# DC-DC_Converters.net
KiCad netlist of a schematic drawn in Altium Designer
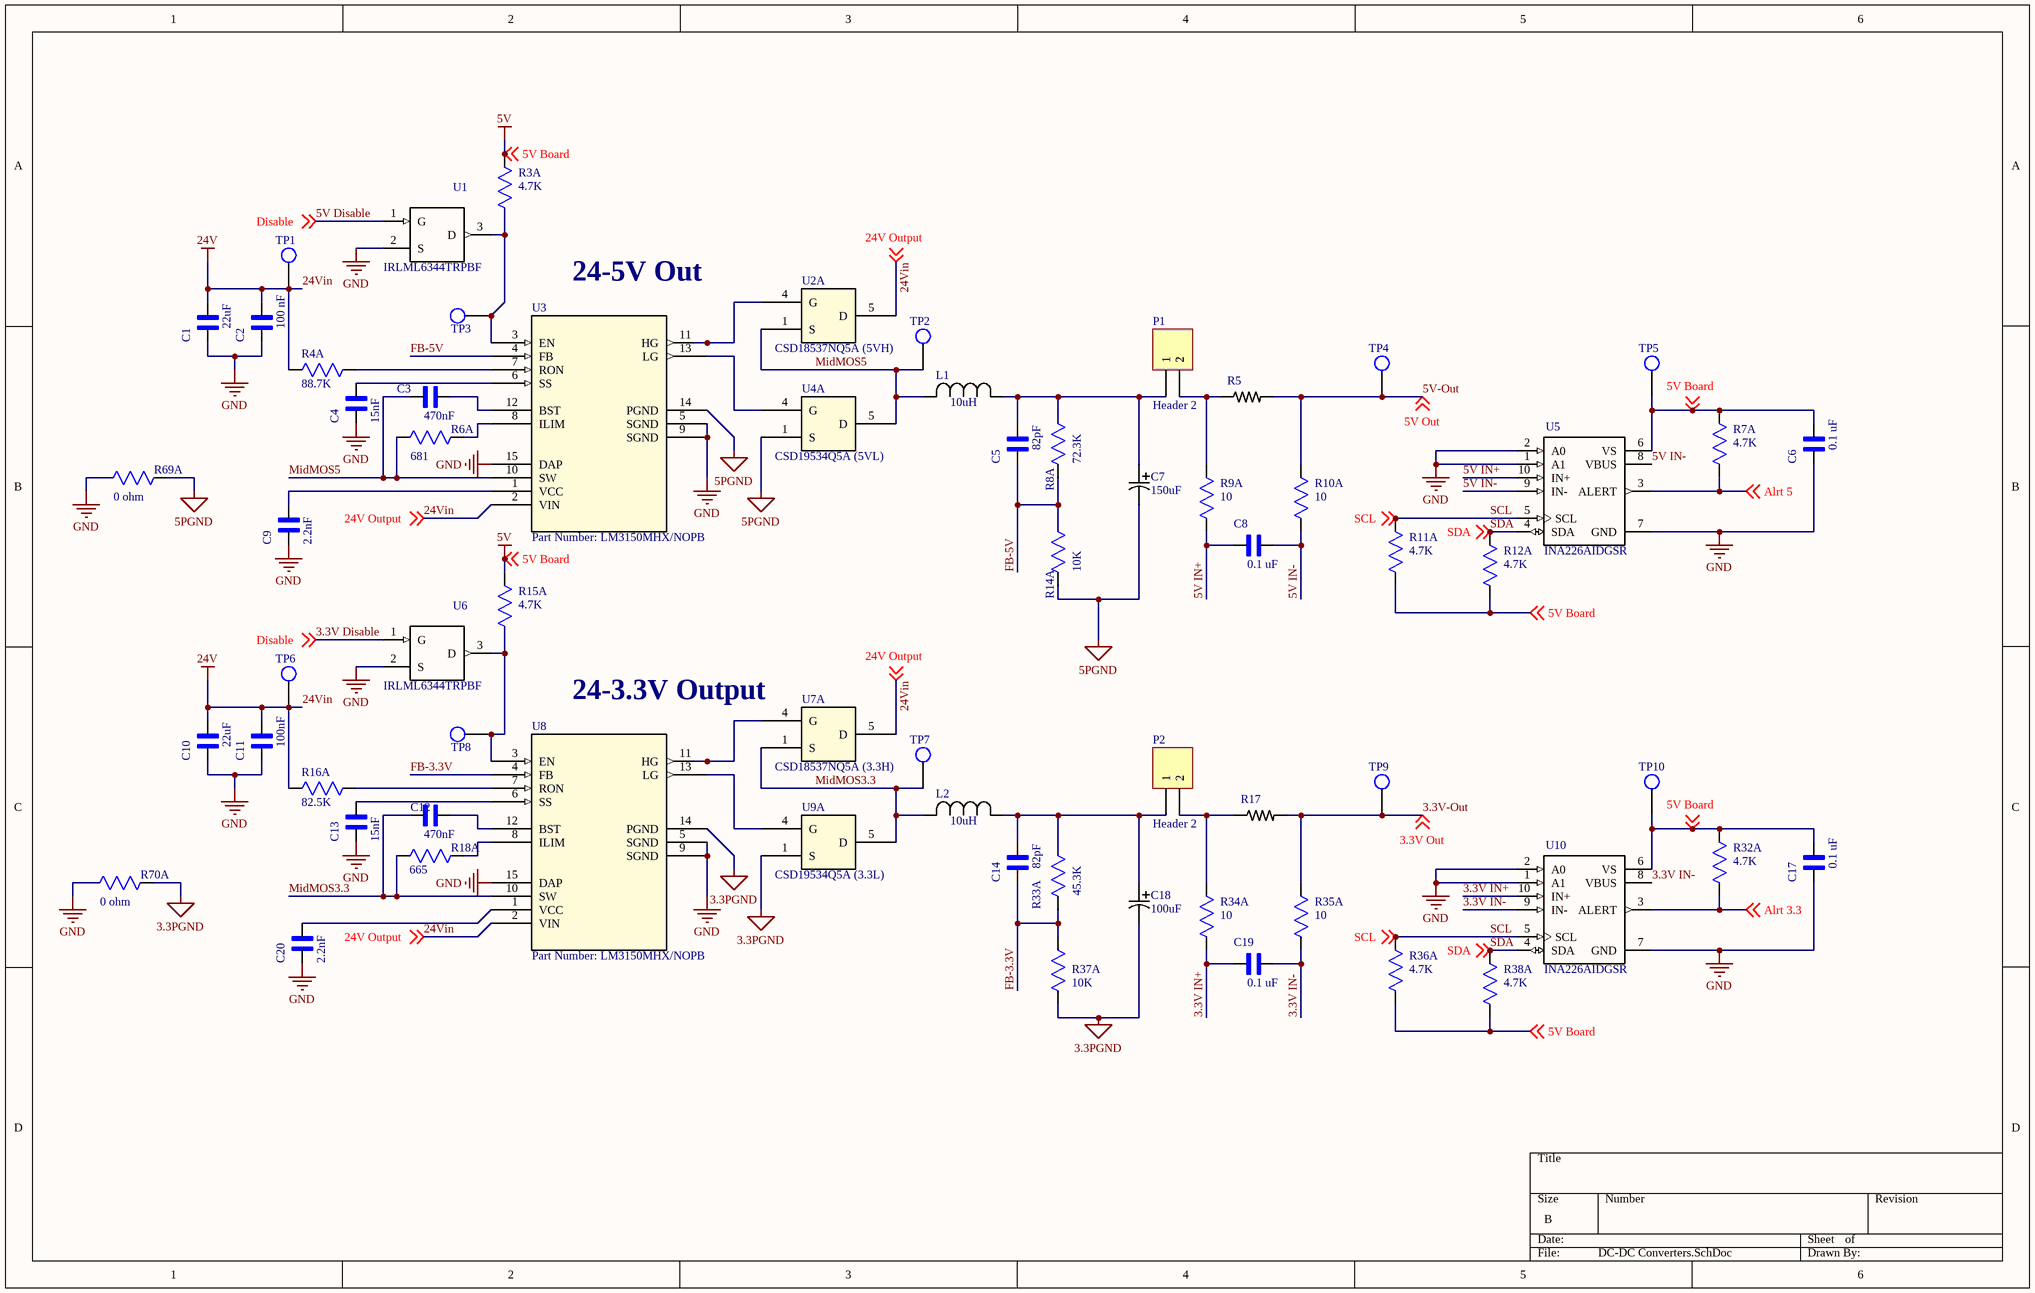
[diagram p0: DC-DC Converters.SchDoc]

(export (version "E")
  (design (tool "Eeschema 10.0.6"))
  (components
    (comp (ref "C1")
      (value "22uF")
      (footprint "*CAPC2012X135N")
      (description "Cap Ceramic 2.2uF 16V X5R 10% SMD 0805 125Â°C Embossed T/R")
      (fields (field (name "MP") "EMK212BJ225KG-T") (field (name "DIGI-KEY_PART_NUMBER") "587-1293-1-ND"))
      (libsource (lib "EMK212BJ225KG-T") (part "EMK212BJ225KG-T"))
    )
    (comp (ref "C2")
      (value "100 nF")
      (footprint "*CAPC2012X135N")
      (description "Cap Ceramic 2.2uF 16V X5R 10% SMD 0805 125Â°C Embossed T/R")
      (fields (field (name "MP") "EMK212BJ225KG-T") (field (name "DIGI-KEY_PART_NUMBER") "587-1293-1-ND"))
      (libsource (lib "EMK212BJ225KG-T") (part "EMK212BJ225KG-T"))
    )
    (comp (ref "C3")
      (value "470nF")
      (footprint "*CAPC2012X135N")
      (description "Cap Ceramic 2.2uF 16V X5R 10% SMD 0805 125Â°C Embossed T/R")
      (fields (field (name "MP") "EMK212BJ225KG-T") (field (name "DIGI-KEY_PART_NUMBER") "587-1293-1-ND"))
      (libsource (lib "EMK212BJ225KG-T") (part "EMK212BJ225KG-T"))
    )
    (comp (ref "C4")
      (value "15nF")
      (footprint "*CAPC2012X135N")
      (description "Cap Ceramic 2.2uF 16V X5R 10% SMD 0805 125Â°C Embossed T/R")
      (fields (field (name "MP") "EMK212BJ225KG-T") (field (name "DIGI-KEY_PART_NUMBER") "587-1293-1-ND"))
      (libsource (lib "EMK212BJ225KG-T") (part "EMK212BJ225KG-T"))
    )
    (comp (ref "C5")
      (value "82pF")
      (footprint "*CAPC2012X135N")
      (description "Cap Ceramic 2.2uF 16V X5R 10% SMD 0805 125Â°C Embossed T/R")
      (fields (field (name "MP") "EMK212BJ225KG-T") (field (name "DIGI-KEY_PART_NUMBER") "587-1293-1-ND"))
      (libsource (lib "EMK212BJ225KG-T") (part "EMK212BJ225KG-T"))
    )
    (comp (ref "C6")
      (value "0.1 uF")
      (footprint "*CAPC2012X135N")
      (description "Cap Ceramic 2.2uF 16V X5R 10% SMD 0805 125Â°C Embossed T/R")
      (fields (field (name "MP") "EMK212BJ225KG-T") (field (name "DIGI-KEY_PART_NUMBER") "587-1293-1-ND"))
      (libsource (lib "EMK212BJ225KG-T") (part "EMK212BJ225KG-T"))
    )
    (comp (ref "C7")
      (value "150uF")
      (footprint "PCAP_TPE_B2")
      (description "No Description Available")
      (fields
        (field (name "MANUFACTURER_PART_NUMBER") "6TPE150MAPB")
        (field (name "COPYRIGHT") "Copyright (C) 2018 Accelerated Designs. All rights reserved")
      )
      (libsource (lib "Pol. Cap 6TPE150MAPB (pkg 1411 (3528 Metric))") (part "6TPE150MAPB"))
    )
    (comp (ref "C8")
      (value "0.1 uF")
      (footprint "*CAPC2012X135N")
      (description "Cap Ceramic 2.2uF 16V X5R 10% SMD 0805 125Â°C Embossed T/R")
      (fields (field (name "MP") "EMK212BJ225KG-T") (field (name "DIGI-KEY_PART_NUMBER") "587-1293-1-ND"))
      (libsource (lib "EMK212BJ225KG-T") (part "EMK212BJ225KG-T"))
    )
    (comp (ref "C9")
      (value "2.2nF")
      (footprint "*CAPC2012X135N")
      (description "Cap Ceramic 2.2uF 16V X5R 10% SMD 0805 125Â°C Embossed T/R")
      (fields (field (name "MP") "EMK212BJ225KG-T") (field (name "DIGI-KEY_PART_NUMBER") "587-1293-1-ND"))
      (libsource (lib "EMK212BJ225KG-T") (part "EMK212BJ225KG-T"))
    )
    (comp (ref "C10")
      (value "22uF")
      (footprint "*CAPC2012X135N")
      (description "Cap Ceramic 2.2uF 16V X5R 10% SMD 0805 125Â°C Embossed T/R")
      (fields (field (name "MP") "EMK212BJ225KG-T") (field (name "DIGI-KEY_PART_NUMBER") "587-1293-1-ND"))
      (libsource (lib "EMK212BJ225KG-T") (part "EMK212BJ225KG-T"))
    )
    (comp (ref "C11")
      (value "100nF")
      (footprint "*CAPC2012X135N")
      (description "Cap Ceramic 2.2uF 16V X5R 10% SMD 0805 125Â°C Embossed T/R")
      (fields (field (name "MP") "EMK212BJ225KG-T") (field (name "DIGI-KEY_PART_NUMBER") "587-1293-1-ND"))
      (libsource (lib "EMK212BJ225KG-T") (part "EMK212BJ225KG-T"))
    )
    (comp (ref "C12")
      (value "470nF")
      (footprint "*CAPC2012X135N")
      (description "Cap Ceramic 2.2uF 16V X5R 10% SMD 0805 125Â°C Embossed T/R")
      (fields (field (name "MP") "EMK212BJ225KG-T") (field (name "DIGI-KEY_PART_NUMBER") "587-1293-1-ND"))
      (libsource (lib "EMK212BJ225KG-T") (part "EMK212BJ225KG-T"))
    )
    (comp (ref "C13")
      (value "15nF")
      (footprint "*CAPC2012X135N")
      (description "Cap Ceramic 2.2uF 16V X5R 10% SMD 0805 125Â°C Embossed T/R")
      (fields (field (name "MP") "EMK212BJ225KG-T") (field (name "DIGI-KEY_PART_NUMBER") "587-1293-1-ND"))
      (libsource (lib "EMK212BJ225KG-T") (part "EMK212BJ225KG-T"))
    )
    (comp (ref "C14")
      (value "82pF")
      (footprint "*CAPC2012X135N")
      (description "Cap Ceramic 2.2uF 16V X5R 10% SMD 0805 125Â°C Embossed T/R")
      (fields (field (name "MP") "EMK212BJ225KG-T") (field (name "DIGI-KEY_PART_NUMBER") "587-1293-1-ND"))
      (libsource (lib "EMK212BJ225KG-T") (part "EMK212BJ225KG-T"))
    )
    (comp (ref "C17")
      (value "0.1 uF")
      (footprint "*CAPC2012X135N")
      (description "Cap Ceramic 2.2uF 16V X5R 10% SMD 0805 125Â°C Embossed T/R")
      (fields (field (name "MP") "EMK212BJ225KG-T") (field (name "DIGI-KEY_PART_NUMBER") "587-1293-1-ND"))
      (libsource (lib "EMK212BJ225KG-T") (part "EMK212BJ225KG-T"))
    )
    (comp (ref "C18")
      (value "100uF")
      (footprint "PCAP_TPE_B2")
      (description "No Description Available")
      (fields
        (field (name "MANUFACTURER_PART_NUMBER") "6TPE150MAPB")
        (field (name "COPYRIGHT") "Copyright (C) 2018 Accelerated Designs. All rights reserved")
      )
      (libsource (lib "Pol. Cap 6TPE150MAPB (pkg 1411 (3528 Metric))") (part "6TPE150MAPB"))
    )
    (comp (ref "C19")
      (value "0.1 uF")
      (footprint "*CAPC2012X135N")
      (description "Cap Ceramic 2.2uF 16V X5R 10% SMD 0805 125Â°C Embossed T/R")
      (fields (field (name "MP") "EMK212BJ225KG-T") (field (name "DIGI-KEY_PART_NUMBER") "587-1293-1-ND"))
      (libsource (lib "EMK212BJ225KG-T") (part "EMK212BJ225KG-T"))
    )
    (comp (ref "C20")
      (value "2.2nF")
      (footprint "*CAPC2012X135N")
      (description "Cap Ceramic 2.2uF 16V X5R 10% SMD 0805 125Â°C Embossed T/R")
      (fields (field (name "MP") "EMK212BJ225KG-T") (field (name "DIGI-KEY_PART_NUMBER") "587-1293-1-ND"))
      (libsource (lib "EMK212BJ225KG-T") (part "EMK212BJ225KG-T"))
    )
    (comp (ref "L1")
      (value "10uH")
      (footprint "IND_BOURNS_SRP12")
      (description "No Description Available")
      (fields
        (field (name "MANUFACTURER_PART_NUMBER") "SRP1250-100M")
        (field (name "COPYRIGHT") "Copyright (C) 2018 Accelerated Designs. All rights reserved")
      )
      (libsource (lib "Inductor SRP1250-100M") (part "SRP1250-100M"))
    )
    (comp (ref "L2")
      (value "10uH")
      (footprint "IND_BOURNS_SRP12")
      (description "No Description Available")
      (fields
        (field (name "MANUFACTURER_PART_NUMBER") "SRP1250-100M")
        (field (name "COPYRIGHT") "Copyright (C) 2018 Accelerated Designs. All rights reserved")
      )
      (libsource (lib "Inductor SRP1250-100M") (part "SRP1250-100M"))
    )
    (comp (ref "P1")
      (value "Header 2")
      (footprint "HDR1X2")
      (description "Header, 2-Pin")
      (fields (field (name "PUBLISHER") "Altium Limited"))
      (libsource (lib "Miscellaneous Connectors") (part "Header 2"))
    )
    (comp (ref "P2")
      (value "Header 2")
      (footprint "HDR1X2")
      (description "Header, 2-Pin")
      (fields (field (name "PUBLISHER") "Altium Limited"))
      (libsource (lib "Miscellaneous Connectors") (part "Header 2"))
    )
    (comp (ref "R3")
      (value "4.7K")
      (footprint "RC0805N")
      (description "No Description Available")
      (fields
        (field (name "MANUFACTURER_PART_NUMBER") "CRCW0805681RFKEA_1")
        (field (name "COPYRIGHT") "Copyright (C) 2018 Accelerated Designs. All rights reserved")
      )
      (libsource (lib "2019-11-21_04-54-07") (part "CRCW0805681RFKEA"))
    )
    (comp (ref "R4")
      (value "88.7K")
      (footprint "RC0805N")
      (description "No Description Available")
      (fields
        (field (name "MANUFACTURER_PART_NUMBER") "CRCW0805681RFKEA_1")
        (field (name "COPYRIGHT") "Copyright (C) 2018 Accelerated Designs. All rights reserved")
      )
      (libsource (lib "2019-11-21_04-54-07") (part "CRCW0805681RFKEA"))
    )
    (comp (ref "R5")
      (value "1-1879378-2")
      (footprint "*RESC6331X70N")
      (description "TLR 2512 2.0W R003 1% 150PPM 2K RL")
      (fields (field (name "MP") "TLR3A20KR003FTDG") (field (name "MF") "TE Connectivity"))
      (libsource (lib "TLR3A20KR003FTDG") (part "TLR3A20KR003FTDG"))
    )
    (comp (ref "R6")
      (value "681")
      (footprint "RC0805N")
      (description "No Description Available")
      (fields
        (field (name "MANUFACTURER_PART_NUMBER") "CRCW0805681RFKEA_1")
        (field (name "COPYRIGHT") "Copyright (C) 2018 Accelerated Designs. All rights reserved")
      )
      (libsource (lib "2019-11-21_04-54-07") (part "CRCW0805681RFKEA"))
    )
    (comp (ref "R7")
      (value "4.7K")
      (footprint "RC0805N")
      (description "No Description Available")
      (fields
        (field (name "MANUFACTURER_PART_NUMBER") "CRCW0805681RFKEA_1")
        (field (name "COPYRIGHT") "Copyright (C) 2018 Accelerated Designs. All rights reserved")
      )
      (libsource (lib "2019-11-21_04-54-07") (part "CRCW0805681RFKEA"))
    )
    (comp (ref "R8")
      (value "72.3K")
      (footprint "RC0805N")
      (description "No Description Available")
      (fields
        (field (name "MANUFACTURER_PART_NUMBER") "CRCW0805681RFKEA_1")
        (field (name "COPYRIGHT") "Copyright (C) 2018 Accelerated Designs. All rights reserved")
      )
      (libsource (lib "2019-11-21_04-54-07") (part "CRCW0805681RFKEA"))
    )
    (comp (ref "R9")
      (value "10")
      (footprint "RC0805N")
      (description "No Description Available")
      (fields
        (field (name "MANUFACTURER_PART_NUMBER") "CRCW0805681RFKEA_1")
        (field (name "COPYRIGHT") "Copyright (C) 2018 Accelerated Designs. All rights reserved")
      )
      (libsource (lib "2019-11-21_04-54-07") (part "CRCW0805681RFKEA"))
    )
    (comp (ref "R10")
      (value "10")
      (footprint "RC0805N")
      (description "No Description Available")
      (fields
        (field (name "MANUFACTURER_PART_NUMBER") "CRCW0805681RFKEA_1")
        (field (name "COPYRIGHT") "Copyright (C) 2018 Accelerated Designs. All rights reserved")
      )
      (libsource (lib "2019-11-21_04-54-07") (part "CRCW0805681RFKEA"))
    )
    (comp (ref "R11")
      (value "4.7K")
      (footprint "RC0805N")
      (description "No Description Available")
      (fields
        (field (name "MANUFACTURER_PART_NUMBER") "CRCW0805681RFKEA_1")
        (field (name "COPYRIGHT") "Copyright (C) 2018 Accelerated Designs. All rights reserved")
      )
      (libsource (lib "2019-11-21_04-54-07") (part "CRCW0805681RFKEA"))
    )
    (comp (ref "R12")
      (value "4.7K")
      (footprint "RC0805N")
      (description "No Description Available")
      (fields
        (field (name "MANUFACTURER_PART_NUMBER") "CRCW0805681RFKEA_1")
        (field (name "COPYRIGHT") "Copyright (C) 2018 Accelerated Designs. All rights reserved")
      )
      (libsource (lib "2019-11-21_04-54-07") (part "CRCW0805681RFKEA"))
    )
    (comp (ref "R14")
      (value "10K")
      (footprint "RC0805N")
      (description "No Description Available")
      (fields
        (field (name "MANUFACTURER_PART_NUMBER") "CRCW0805681RFKEA_1")
        (field (name "COPYRIGHT") "Copyright (C) 2018 Accelerated Designs. All rights reserved")
      )
      (libsource (lib "2019-11-21_04-54-07") (part "CRCW0805681RFKEA"))
    )
    (comp (ref "R15")
      (value "4.7K")
      (footprint "RC0805N")
      (description "No Description Available")
      (fields
        (field (name "MANUFACTURER_PART_NUMBER") "CRCW0805681RFKEA_1")
        (field (name "COPYRIGHT") "Copyright (C) 2018 Accelerated Designs. All rights reserved")
      )
      (libsource (lib "2019-11-21_04-54-07") (part "CRCW0805681RFKEA"))
    )
    (comp (ref "R16")
      (value "82.5K")
      (footprint "RC0805N")
      (description "No Description Available")
      (fields
        (field (name "MANUFACTURER_PART_NUMBER") "CRCW0805681RFKEA_1")
        (field (name "COPYRIGHT") "Copyright (C) 2018 Accelerated Designs. All rights reserved")
      )
      (libsource (lib "2019-11-21_04-54-07") (part "CRCW0805681RFKEA"))
    )
    (comp (ref "R17")
      (value "1-1879378-2")
      (footprint "*RESC6331X70N")
      (description "TLR 2512 2.0W R003 1% 150PPM 2K RL")
      (fields (field (name "MP") "TLR3A20KR003FTDG") (field (name "MF") "TE Connectivity"))
      (libsource (lib "TLR3A20KR003FTDG") (part "TLR3A20KR003FTDG"))
    )
    (comp (ref "R18")
      (value "665")
      (footprint "RC0805N")
      (description "No Description Available")
      (fields
        (field (name "MANUFACTURER_PART_NUMBER") "CRCW0805681RFKEA_1")
        (field (name "COPYRIGHT") "Copyright (C) 2018 Accelerated Designs. All rights reserved")
      )
      (libsource (lib "2019-11-21_04-54-07") (part "CRCW0805681RFKEA"))
    )
    (comp (ref "R32")
      (value "4.7K")
      (footprint "RC0805N")
      (description "No Description Available")
      (fields
        (field (name "MANUFACTURER_PART_NUMBER") "CRCW0805681RFKEA_1")
        (field (name "COPYRIGHT") "Copyright (C) 2018 Accelerated Designs. All rights reserved")
      )
      (libsource (lib "2019-11-21_04-54-07") (part "CRCW0805681RFKEA"))
    )
    (comp (ref "R33")
      (value "45.3K")
      (footprint "RC0805N")
      (description "No Description Available")
      (fields
        (field (name "MANUFACTURER_PART_NUMBER") "CRCW0805681RFKEA_1")
        (field (name "COPYRIGHT") "Copyright (C) 2018 Accelerated Designs. All rights reserved")
      )
      (libsource (lib "2019-11-21_04-54-07") (part "CRCW0805681RFKEA"))
    )
    (comp (ref "R34")
      (value "10")
      (footprint "RC0805N")
      (description "No Description Available")
      (fields
        (field (name "MANUFACTURER_PART_NUMBER") "CRCW0805681RFKEA_1")
        (field (name "COPYRIGHT") "Copyright (C) 2018 Accelerated Designs. All rights reserved")
      )
      (libsource (lib "2019-11-21_04-54-07") (part "CRCW0805681RFKEA"))
    )
    (comp (ref "R35")
      (value "10")
      (footprint "RC0805N")
      (description "No Description Available")
      (fields
        (field (name "MANUFACTURER_PART_NUMBER") "CRCW0805681RFKEA_1")
        (field (name "COPYRIGHT") "Copyright (C) 2018 Accelerated Designs. All rights reserved")
      )
      (libsource (lib "2019-11-21_04-54-07") (part "CRCW0805681RFKEA"))
    )
    (comp (ref "R36")
      (value "4.7K")
      (footprint "RC0805N")
      (description "No Description Available")
      (fields
        (field (name "MANUFACTURER_PART_NUMBER") "CRCW0805681RFKEA_1")
        (field (name "COPYRIGHT") "Copyright (C) 2018 Accelerated Designs. All rights reserved")
      )
      (libsource (lib "2019-11-21_04-54-07") (part "CRCW0805681RFKEA"))
    )
    (comp (ref "R37")
      (value "10K")
      (footprint "RC0805N")
      (description "No Description Available")
      (fields
        (field (name "MANUFACTURER_PART_NUMBER") "CRCW0805681RFKEA_1")
        (field (name "COPYRIGHT") "Copyright (C) 2018 Accelerated Designs. All rights reserved")
      )
      (libsource (lib "2019-11-21_04-54-07") (part "CRCW0805681RFKEA"))
    )
    (comp (ref "R38")
      (value "4.7K")
      (footprint "RC0805N")
      (description "No Description Available")
      (fields
        (field (name "MANUFACTURER_PART_NUMBER") "CRCW0805681RFKEA_1")
        (field (name "COPYRIGHT") "Copyright (C) 2018 Accelerated Designs. All rights reserved")
      )
      (libsource (lib "2019-11-21_04-54-07") (part "CRCW0805681RFKEA"))
    )
    (comp (ref "R69")
      (value "0 ohm")
      (footprint "RC0805N")
      (description "No Description Available")
      (fields
        (field (name "MANUFACTURER_PART_NUMBER") "CRCW0805681RFKEA_1")
        (field (name "COPYRIGHT") "Copyright (C) 2018 Accelerated Designs. All rights reserved")
      )
      (libsource (lib "2019-11-21_04-54-07") (part "CRCW0805681RFKEA"))
    )
    (comp (ref "R70")
      (value "0 ohm")
      (footprint "RC0805N")
      (description "No Description Available")
      (fields
        (field (name "MANUFACTURER_PART_NUMBER") "CRCW0805681RFKEA_1")
        (field (name "COPYRIGHT") "Copyright (C) 2018 Accelerated Designs. All rights reserved")
      )
      (libsource (lib "2019-11-21_04-54-07") (part "CRCW0805681RFKEA"))
    )
    (comp (ref "TP1")
      (value "Test Point")
      (footprint "Test Point Through-hole")
      (libsource (lib "Test Points") (part "Test Point"))
    )
    (comp (ref "TP2")
      (value "Test Point")
      (footprint "Test Point Through-hole")
      (libsource (lib "Test Points") (part "Test Point"))
    )
    (comp (ref "TP3")
      (value "Test Point")
      (footprint "Test Point Through-hole")
      (libsource (lib "Test Points") (part "Test Point"))
    )
    (comp (ref "TP4")
      (value "Test Point")
      (footprint "Test Point Through-hole")
      (libsource (lib "Test Points") (part "Test Point"))
    )
    (comp (ref "TP5")
      (value "Test Point")
      (footprint "Test Point Through-hole")
      (libsource (lib "Test Points") (part "Test Point"))
    )
    (comp (ref "TP6")
      (value "Test Point")
      (footprint "Test Point Through-hole")
      (libsource (lib "Test Points") (part "Test Point"))
    )
    (comp (ref "TP7")
      (value "Test Point")
      (footprint "Test Point Through-hole")
      (libsource (lib "Test Points") (part "Test Point"))
    )
    (comp (ref "TP8")
      (value "Test Point")
      (footprint "Test Point Through-hole")
      (libsource (lib "Test Points") (part "Test Point"))
    )
    (comp (ref "TP9")
      (value "Test Point")
      (footprint "Test Point Through-hole")
      (libsource (lib "Test Points") (part "Test Point"))
    )
    (comp (ref "TP10")
      (value "Test Point")
      (footprint "Test Point Through-hole")
      (libsource (lib "Test Points") (part "Test Point"))
    )
    (comp (ref "U1")
      (value "IRLML6344TRPBF")
      (footprint "*SOT95P240X112-3N")
      (description "IRLML6344TRPBF N-channel MOSFET Transistor, 5 A, 30 V, 3-Pin SOT-23")
      (fields
        (field (name "MF") "Infineon Technologies")
        (field (name "DIGI-KEY_PART_NUMBER") "IRLML6344TRPBFCT-ND")
      )
      (libsource (lib "Power MOS for EN") (part "IRLML6344TRPBF"))
    )
    (comp (ref "U2")
      (value "CSD18537NQ5A (5VH)")
      (footprint "*TRANS_BSC076N06NS3-G")
      (description "No Description Available")
      (fields
        (field (name "MANUFACTURER_PART_NUMBER") "CSD18537NQ5A")
        (field (name "COPYRIGHT") "Copyright (C) 2018 Accelerated Designs. All rights reserved")
      )
      (libsource (lib "NMOS - CSB18537NQ5A (5V H)") (part "CSD18537NQ5A"))
    )
    (comp (ref "U3")
      (value "Part Number: LM3150MHX/NOPB")
      (footprint "MXA14A")
      (description "No Description Available")
      (fields
        (field (name "MANUFACTURER_PART_NUMBER") "LM3150MHX/NOPB")
        (field (name "COPYRIGHT") "Copyright (C) 2018 Accelerated Designs. All rights reserved")
      )
      (libsource (lib "LM3150 - Buck Converter Controller (Functional)") (part "LM3150MHX/NOPB"))
    )
    (comp (ref "U4")
      (value "CSD19534Q5A (5VL)")
      (footprint "DQJ8")
      (description "No Description Available")
      (fields
        (field (name "MANUFACTURER_PART_NUMBER") "CSD19534Q5A")
        (field (name "COPYRIGHT") "Copyright (C) 2018 Accelerated Designs. All rights reserved")
      )
      (libsource (lib "NMOS - CSD19534Q5A (5V L)") (part "CSD19534Q5A"))
    )
    (comp (ref "U5")
      (value "INA226AIDGSR")
      (footprint "*SOP50P490X110-10N")
      (description "Current Monitor Regulator High/Low-Side 10mA 10-VSSOP")
      (fields (field (name "MF") "Texas Instruments") (field (name "DIGI-KEY_PART_NUMBER") "296-29034-1-ND"))
      (libsource (lib "INA226AIDGSR") (part "INA226AIDGSR"))
    )
    (comp (ref "U6")
      (value "IRLML6344TRPBF")
      (footprint "*SOT95P240X112-3N")
      (description "IRLML6344TRPBF N-channel MOSFET Transistor, 5 A, 30 V, 3-Pin SOT-23")
      (fields
        (field (name "MF") "Infineon Technologies")
        (field (name "DIGI-KEY_PART_NUMBER") "IRLML6344TRPBFCT-ND")
      )
      (libsource (lib "Power MOS for EN") (part "IRLML6344TRPBF"))
    )
    (comp (ref "U7")
      (value "CSD18537NQ5A (3.3H)")
      (footprint "DQJ8")
      (description "No Description Available")
      (fields
        (field (name "MANUFACTURER_PART_NUMBER") "CSD18537NQ5A")
        (field (name "COPYRIGHT") "Copyright (C) 2018 Accelerated Designs. All rights reserved")
      )
      (libsource (lib "NMOS - CSB18537NQ5A (5V H)") (part "CSD18537NQ5A"))
    )
    (comp (ref "U8")
      (value "Part Number: LM3150MHX/NOPB")
      (footprint "MXA14A")
      (description "No Description Available")
      (fields
        (field (name "MANUFACTURER_PART_NUMBER") "LM3150MHX/NOPB")
        (field (name "COPYRIGHT") "Copyright (C) 2018 Accelerated Designs. All rights reserved")
      )
      (libsource (lib "LM3150 - Buck Converter Controller (Functional)") (part "LM3150MHX/NOPB"))
    )
    (comp (ref "U9")
      (value "CSD19534Q5A (3.3L)")
      (footprint "DQJ8")
      (description "No Description Available")
      (fields
        (field (name "MANUFACTURER_PART_NUMBER") "CSD19534Q5A")
        (field (name "COPYRIGHT") "Copyright (C) 2018 Accelerated Designs. All rights reserved")
      )
      (libsource (lib "NMOS - CSD19534Q5A (5V L)") (part "CSD19534Q5A"))
    )
    (comp (ref "U10")
      (value "INA226AIDGSR")
      (footprint "*SOP50P490X110-10N")
      (description "Current Monitor Regulator High/Low-Side 10mA 10-VSSOP")
      (fields (field (name "MF") "Texas Instruments") (field (name "DIGI-KEY_PART_NUMBER") "296-29034-1-ND"))
      (libsource (lib "INA226AIDGSR") (part "INA226AIDGSR"))
    )
  )
  (nets
    (net (code "1") (name "/3.3V IN+") (class "Default")
      (node (ref "C19") (pin "1") (pinfunction "1_1") (pintype "passive"))
      (node (ref "U10") (pin "10") (pinfunction "IN+_10") (pintype "input"))
    )
    (net (code "2") (name "/3.3V IN-") (class "Default")
      (node (ref "C19") (pin "2") (pinfunction "2_2") (pintype "passive"))
      (node (ref "U10") (pin "8") (pinfunction "VBUS_8") (pintype "power_in"))
      (node (ref "U10") (pin "9") (pinfunction "IN-_9") (pintype "input"))
    )
    (net (code "3") (name "/5V IN+") (class "Default")
      (node (ref "C8") (pin "1") (pinfunction "1_1") (pintype "passive"))
      (node (ref "U5") (pin "10") (pinfunction "IN+_10") (pintype "input"))
    )
    (net (code "4") (name "/5V IN-") (class "Default")
      (node (ref "C8") (pin "2") (pinfunction "2_2") (pintype "passive"))
      (node (ref "U5") (pin "8") (pinfunction "VBUS_8") (pintype "power_in"))
      (node (ref "U5") (pin "9") (pinfunction "IN-_9") (pintype "input"))
    )
    (net (code "5") (name "/FB-3.3V") (class "Default")
      (node (ref "C14") (pin "1") (pinfunction "1_1") (pintype "passive"))
      (node (ref "R33") (pin "1") (pinfunction "1_1") (pintype "passive"))
      (node (ref "R37") (pin "1") (pinfunction "1_1") (pintype "passive"))
      (node (ref "U8") (pin "4") (pinfunction "FB_4") (pintype "input"))
    )
    (net (code "6") (name "/FB-5V") (class "Default")
      (node (ref "C5") (pin "1") (pinfunction "1_1") (pintype "passive"))
      (node (ref "R14") (pin "2") (pinfunction "2_2") (pintype "passive"))
      (node (ref "R8") (pin "1") (pinfunction "1_1") (pintype "passive"))
      (node (ref "U3") (pin "4") (pinfunction "FB_4") (pintype "input"))
    )
    (net (code "7") (name "/MidMOS3.3") (class "Default")
      (node (ref "C12") (pin "1") (pinfunction "1_1") (pintype "passive"))
      (node (ref "L2") (pin "2") (pinfunction "2_2") (pintype "passive"))
      (node (ref "TP7") (pin "1") (pinfunction "1_1") (pintype "passive"))
      (node (ref "U7") (pin "1") (pinfunction "S_1") (pintype "passive"))
      (node (ref "U8") (pin "10") (pinfunction "SW_10") (pintype "power_in"))
      (node (ref "U9") (pin "5") (pinfunction "D_5") (pintype "passive"))
    )
    (net (code "8") (name "/MidMOS5") (class "Default")
      (node (ref "C3") (pin "1") (pinfunction "1_1") (pintype "passive"))
      (node (ref "L1") (pin "2") (pinfunction "2_2") (pintype "passive"))
      (node (ref "TP2") (pin "1") (pinfunction "1_1") (pintype "passive"))
      (node (ref "U2") (pin "1") (pinfunction "S_1") (pintype "passive"))
      (node (ref "U3") (pin "10") (pinfunction "SW_10") (pintype "power_in"))
      (node (ref "U4") (pin "5") (pinfunction "D_5") (pintype "passive"))
    )
    (net (code "9") (name "3.3PGND") (class "Default")
      (node (ref "C18") (pin "2") (pinfunction "2_2") (pintype "passive"))
      (node (ref "R70") (pin "1") (pinfunction "1_1") (pintype "passive"))
      (node (ref "U8") (pin "14") (pinfunction "PGND_14") (pintype "power_in"))
      (node (ref "U9") (pin "1") (pinfunction "S_1") (pintype "passive"))
    )
    (net (code "10") (name "3.3V Out") (class "Default")
      (node (ref "R17") (pin "2") (pinfunction "2_2") (pintype "passive"))
      (node (ref "R35") (pin "1") (pinfunction "1_1") (pintype "passive"))
      (node (ref "TP9") (pin "1") (pinfunction "1_1") (pintype "passive"))
    )
    (net (code "11") (name "5PGND") (class "Default")
      (node (ref "C7") (pin "2") (pinfunction "2_2") (pintype "passive"))
      (node (ref "R14") (pin "1") (pinfunction "1_1") (pintype "passive"))
      (node (ref "R69") (pin "1") (pinfunction "1_1") (pintype "passive"))
      (node (ref "U3") (pin "14") (pinfunction "PGND_14") (pintype "power_in"))
      (node (ref "U4") (pin "1") (pinfunction "S_1") (pintype "passive"))
    )
    (net (code "12") (name "5V") (class "Default")
      (node (ref "C17") (pin "2") (pinfunction "2_2") (pintype "passive"))
      (node (ref "C6") (pin "2") (pinfunction "2_2") (pintype "passive"))
      (node (ref "R15") (pin "1") (pinfunction "1_1") (pintype "passive"))
      (node (ref "R3") (pin "1") (pinfunction "1_1") (pintype "passive"))
      (node (ref "R32") (pin "1") (pinfunction "1_1") (pintype "passive"))
      (node (ref "R7") (pin "1") (pinfunction "1_1") (pintype "passive"))
      (node (ref "TP10") (pin "1") (pinfunction "1_1") (pintype "passive"))
      (node (ref "TP5") (pin "1") (pinfunction "1_1") (pintype "passive"))
      (node (ref "U10") (pin "6") (pinfunction "VS_6") (pintype "power_in"))
      (node (ref "U5") (pin "6") (pinfunction "VS_6") (pintype "power_in"))
    )
    (net (code "13") (name "5V Out") (class "Default")
      (node (ref "R10") (pin "1") (pinfunction "1_1") (pintype "passive"))
      (node (ref "R5") (pin "2") (pinfunction "2_2") (pintype "passive"))
      (node (ref "TP4") (pin "1") (pinfunction "1_1") (pintype "passive"))
    )
    (net (code "14") (name "24V") (class "Default")
      (node (ref "C1") (pin "2") (pinfunction "2_2") (pintype "passive"))
      (node (ref "C10") (pin "2") (pinfunction "2_2") (pintype "passive"))
      (node (ref "C11") (pin "2") (pinfunction "2_2") (pintype "passive"))
      (node (ref "C2") (pin "2") (pinfunction "2_2") (pintype "passive"))
      (node (ref "TP1") (pin "1") (pinfunction "1_1") (pintype "passive"))
      (node (ref "TP6") (pin "1") (pinfunction "1_1") (pintype "passive"))
      (node (ref "U2") (pin "5") (pinfunction "D_5") (pintype "passive"))
      (node (ref "U3") (pin "2") (pinfunction "VIN_2") (pintype "power_in"))
      (node (ref "U7") (pin "5") (pinfunction "D_5") (pintype "passive"))
      (node (ref "U8") (pin "2") (pinfunction "VIN_2") (pintype "power_in"))
    )
    (net (code "15") (name "Alrt 3.3") (class "Default")
      (node (ref "U10") (pin "3") (pinfunction "ALERT_3") (pintype "output"))
    )
    (net (code "16") (name "Alrt 5") (class "Default")
      (node (ref "U5") (pin "3") (pinfunction "ALERT_3") (pintype "output"))
    )
    (net (code "17") (name "Disable") (class "Default")
      (node (ref "U1") (pin "1") (pinfunction "G_1") (pintype "input"))
      (node (ref "U6") (pin "1") (pinfunction "G_1") (pintype "input"))
    )
    (net (code "18") (name "GND") (class "Default")
      (node (ref "C1") (pin "1") (pinfunction "1_1") (pintype "passive"))
      (node (ref "C10") (pin "1") (pinfunction "1_1") (pintype "passive"))
      (node (ref "C11") (pin "1") (pinfunction "1_1") (pintype "passive"))
      (node (ref "C13") (pin "1") (pinfunction "1_1") (pintype "passive"))
      (node (ref "C17") (pin "1") (pinfunction "1_1") (pintype "passive"))
      (node (ref "C2") (pin "1") (pinfunction "1_1") (pintype "passive"))
      (node (ref "C20") (pin "1") (pinfunction "1_1") (pintype "passive"))
      (node (ref "C4") (pin "1") (pinfunction "1_1") (pintype "passive"))
      (node (ref "C6") (pin "1") (pinfunction "1_1") (pintype "passive"))
      (node (ref "C9") (pin "1") (pinfunction "1_1") (pintype "passive"))
      (node (ref "R69") (pin "2") (pinfunction "2_2") (pintype "passive"))
      (node (ref "R70") (pin "2") (pinfunction "2_2") (pintype "passive"))
      (node (ref "U1") (pin "2") (pinfunction "S_2") (pintype "passive"))
      (node (ref "U10") (pin "1") (pinfunction "A1_1") (pintype "input"))
      (node (ref "U10") (pin "2") (pinfunction "A0_2") (pintype "input"))
      (node (ref "U10") (pin "7") (pinfunction "GND_7") (pintype "power_in"))
      (node (ref "U3") (pin "15") (pinfunction "DAP_15") (pintype "power_in"))
      (node (ref "U3") (pin "5") (pinfunction "SGND_5") (pintype "power_in"))
      (node (ref "U3") (pin "9") (pinfunction "SGND_9") (pintype "power_in"))
      (node (ref "U5") (pin "1") (pinfunction "A1_1") (pintype "input"))
      (node (ref "U5") (pin "2") (pinfunction "A0_2") (pintype "input"))
      (node (ref "U5") (pin "7") (pinfunction "GND_7") (pintype "power_in"))
      (node (ref "U6") (pin "2") (pinfunction "S_2") (pintype "passive"))
      (node (ref "U8") (pin "15") (pinfunction "DAP_15") (pintype "power_in"))
      (node (ref "U8") (pin "5") (pinfunction "SGND_5") (pintype "power_in"))
      (node (ref "U8") (pin "9") (pinfunction "SGND_9") (pintype "power_in"))
    )
    (net (code "19") (name "Net-(C5-Pad2)") (class "Default")
      (node (ref "C5") (pin "2") (pinfunction "2_2") (pintype "passive"))
      (node (ref "C7") (pin "1") (pinfunction "1_1") (pintype "passive"))
      (node (ref "L1") (pin "1") (pinfunction "1_1") (pintype "passive"))
      (node (ref "P1") (pin "1") (pinfunction "1_1") (pintype "passive"))
      (node (ref "R8") (pin "2") (pinfunction "2_2") (pintype "passive"))
    )
    (net (code "20") (name "Net-(C14-Pad2)") (class "Default")
      (node (ref "C14") (pin "2") (pinfunction "2_2") (pintype "passive"))
      (node (ref "C18") (pin "1") (pinfunction "1_1") (pintype "passive"))
      (node (ref "L2") (pin "1") (pinfunction "1_1") (pintype "passive"))
      (node (ref "P2") (pin "1") (pinfunction "1_1") (pintype "passive"))
      (node (ref "R33") (pin "2") (pinfunction "2_2") (pintype "passive"))
    )
    (net (code "21") (name "Net-(P1-Pad2)") (class "Default")
      (node (ref "P1") (pin "2") (pinfunction "2_2") (pintype "passive"))
      (node (ref "R5") (pin "1") (pinfunction "1_1") (pintype "passive"))
      (node (ref "R9") (pin "1") (pinfunction "1_1") (pintype "passive"))
    )
    (net (code "22") (name "Net-(P2-Pad2)") (class "Default")
      (node (ref "P2") (pin "2") (pinfunction "2_2") (pintype "passive"))
      (node (ref "R17") (pin "1") (pinfunction "1_1") (pintype "passive"))
      (node (ref "R34") (pin "1") (pinfunction "1_1") (pintype "passive"))
    )
    (net (code "23") (name "Net-(U1-D)") (class "Default")
      (node (ref "R3") (pin "2") (pinfunction "2_2") (pintype "passive"))
      (node (ref "TP3") (pin "1") (pinfunction "1_1") (pintype "passive"))
      (node (ref "U1") (pin "3") (pinfunction "D_3") (pintype "output"))
      (node (ref "U3") (pin "3") (pinfunction "EN_3") (pintype "input"))
    )
    (net (code "24") (name "Net-(U2-G)") (class "Default")
      (node (ref "U2") (pin "4") (pinfunction "G_4") (pintype "passive"))
      (node (ref "U3") (pin "11") (pinfunction "HG_11") (pintype "output"))
    )
    (net (code "25") (name "Net-(U3-BST)") (class "Default")
      (node (ref "C3") (pin "2") (pinfunction "2_2") (pintype "passive"))
      (node (ref "U3") (pin "12") (pinfunction "BST_12") (pintype "passive"))
    )
    (net (code "26") (name "Net-(U3-ILIM)") (class "Default")
      (node (ref "R6") (pin "1") (pinfunction "1_1") (pintype "passive"))
      (node (ref "U3") (pin "8") (pinfunction "ILIM_8") (pintype "passive"))
    )
    (net (code "27") (name "Net-(U3-LG)") (class "Default")
      (node (ref "U3") (pin "13") (pinfunction "LG_13") (pintype "output"))
      (node (ref "U4") (pin "4") (pinfunction "G_4") (pintype "passive"))
    )
    (net (code "28") (name "Net-(U3-RON)") (class "Default")
      (node (ref "R4") (pin "1") (pinfunction "1_1") (pintype "passive"))
      (node (ref "U3") (pin "7") (pinfunction "RON_7") (pintype "input"))
    )
    (net (code "29") (name "Net-(U3-SS)") (class "Default")
      (node (ref "C4") (pin "2") (pinfunction "2_2") (pintype "passive"))
      (node (ref "U3") (pin "6") (pinfunction "SS_6") (pintype "input"))
    )
    (net (code "30") (name "Net-(U3-VCC)") (class "Default")
      (node (ref "C9") (pin "2") (pinfunction "2_2") (pintype "passive"))
      (node (ref "U3") (pin "1") (pinfunction "VCC_1") (pintype "power_in"))
    )
    (net (code "31") (name "Net-(U6-D)") (class "Default")
      (node (ref "R15") (pin "2") (pinfunction "2_2") (pintype "passive"))
      (node (ref "TP8") (pin "1") (pinfunction "1_1") (pintype "passive"))
      (node (ref "U6") (pin "3") (pinfunction "D_3") (pintype "output"))
      (node (ref "U8") (pin "3") (pinfunction "EN_3") (pintype "input"))
    )
    (net (code "32") (name "Net-(U7-G)") (class "Default")
      (node (ref "U7") (pin "4") (pinfunction "G_4") (pintype "passive"))
      (node (ref "U8") (pin "11") (pinfunction "HG_11") (pintype "output"))
    )
    (net (code "33") (name "Net-(U8-BST)") (class "Default")
      (node (ref "C12") (pin "2") (pinfunction "2_2") (pintype "passive"))
      (node (ref "U8") (pin "12") (pinfunction "BST_12") (pintype "passive"))
    )
    (net (code "34") (name "Net-(U8-ILIM)") (class "Default")
      (node (ref "R18") (pin "1") (pinfunction "1_1") (pintype "passive"))
      (node (ref "U8") (pin "8") (pinfunction "ILIM_8") (pintype "passive"))
    )
    (net (code "35") (name "Net-(U8-LG)") (class "Default")
      (node (ref "U8") (pin "13") (pinfunction "LG_13") (pintype "output"))
      (node (ref "U9") (pin "4") (pinfunction "G_4") (pintype "passive"))
    )
    (net (code "36") (name "Net-(U8-RON)") (class "Default")
      (node (ref "R16") (pin "1") (pinfunction "1_1") (pintype "passive"))
      (node (ref "U8") (pin "7") (pinfunction "RON_7") (pintype "input"))
    )
    (net (code "37") (name "Net-(U8-SS)") (class "Default")
      (node (ref "C13") (pin "2") (pinfunction "2_2") (pintype "passive"))
      (node (ref "U8") (pin "6") (pinfunction "SS_6") (pintype "input"))
    )
    (net (code "38") (name "Net-(U8-VCC)") (class "Default")
      (node (ref "C20") (pin "2") (pinfunction "2_2") (pintype "passive"))
      (node (ref "U8") (pin "1") (pinfunction "VCC_1") (pintype "power_in"))
    )
    (net (code "39") (name "SCL") (class "Default")
      (node (ref "R11") (pin "1") (pinfunction "1_1") (pintype "passive"))
      (node (ref "R36") (pin "1") (pinfunction "1_1") (pintype "passive"))
      (node (ref "U10") (pin "5") (pinfunction "SCL_5") (pintype "input"))
      (node (ref "U5") (pin "5") (pinfunction "SCL_5") (pintype "input"))
    )
    (net (code "40") (name "SDA") (class "Default")
      (node (ref "R12") (pin "1") (pinfunction "1_1") (pintype "passive"))
      (node (ref "R38") (pin "1") (pinfunction "1_1") (pintype "passive"))
      (node (ref "U10") (pin "4") (pinfunction "SDA_4") (pintype "bidirectional"))
      (node (ref "U5") (pin "4") (pinfunction "SDA_4") (pintype "bidirectional"))
    )
    (net (code "41") (name "unconnected-(R4-Pad2)") (class "Default")
      (node (ref "R4") (pin "2") (pinfunction "2_2") (pintype "passive"))
    )
    (net (code "42") (name "unconnected-(R6-Pad2)") (class "Default")
      (node (ref "R6") (pin "2") (pinfunction "2_2") (pintype "passive"))
    )
    (net (code "43") (name "unconnected-(R7-Pad2)") (class "Default")
      (node (ref "R7") (pin "2") (pinfunction "2_2") (pintype "passive"))
    )
    (net (code "44") (name "unconnected-(R9-Pad2)") (class "Default")
      (node (ref "R9") (pin "2") (pinfunction "2_2") (pintype "passive"))
    )
    (net (code "45") (name "unconnected-(R10-Pad2)") (class "Default")
      (node (ref "R10") (pin "2") (pinfunction "2_2") (pintype "passive"))
    )
    (net (code "46") (name "unconnected-(R11-Pad2)") (class "Default")
      (node (ref "R11") (pin "2") (pinfunction "2_2") (pintype "passive"))
    )
    (net (code "47") (name "unconnected-(R12-Pad2)") (class "Default")
      (node (ref "R12") (pin "2") (pinfunction "2_2") (pintype "passive"))
    )
    (net (code "48") (name "unconnected-(R16-Pad2)") (class "Default")
      (node (ref "R16") (pin "2") (pinfunction "2_2") (pintype "passive"))
    )
    (net (code "49") (name "unconnected-(R18-Pad2)") (class "Default")
      (node (ref "R18") (pin "2") (pinfunction "2_2") (pintype "passive"))
    )
    (net (code "50") (name "unconnected-(R32-Pad2)") (class "Default")
      (node (ref "R32") (pin "2") (pinfunction "2_2") (pintype "passive"))
    )
    (net (code "51") (name "unconnected-(R34-Pad2)") (class "Default")
      (node (ref "R34") (pin "2") (pinfunction "2_2") (pintype "passive"))
    )
    (net (code "52") (name "unconnected-(R35-Pad2)") (class "Default")
      (node (ref "R35") (pin "2") (pinfunction "2_2") (pintype "passive"))
    )
    (net (code "53") (name "unconnected-(R36-Pad2)") (class "Default")
      (node (ref "R36") (pin "2") (pinfunction "2_2") (pintype "passive"))
    )
    (net (code "54") (name "unconnected-(R37-Pad2)") (class "Default")
      (node (ref "R37") (pin "2") (pinfunction "2_2") (pintype "passive"))
    )
    (net (code "55") (name "unconnected-(R38-Pad2)") (class "Default")
      (node (ref "R38") (pin "2") (pinfunction "2_2") (pintype "passive"))
    )
  )
)
